# mux_sh_lite.net
KiCad netlist of a schematic drawn in EAGLE
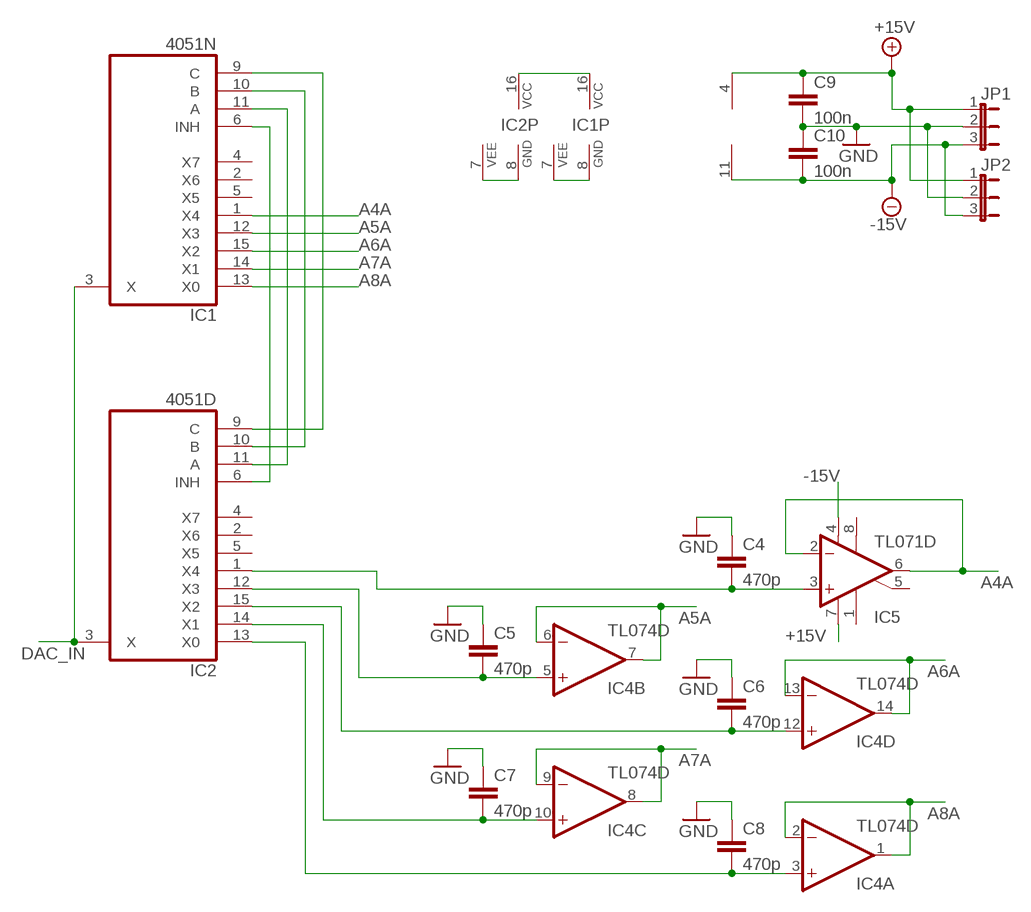
[diagram p0: schematic, sheet 1]

(export (version "E")
  (design (tool "Eeschema 10.0.6"))
  (components
    (comp (ref "C4")
      (value "470p")
      (footprint "eagle-import:0805")
      (libsource (lib "eagle-import") (part "CAP0805"))
    )
    (comp (ref "C5")
      (value "470p")
      (footprint "eagle-import:0805")
      (libsource (lib "eagle-import") (part "CAP0805"))
    )
    (comp (ref "C6")
      (value "470p")
      (footprint "eagle-import:0805")
      (libsource (lib "eagle-import") (part "CAP0805"))
    )
    (comp (ref "C7")
      (value "470p")
      (footprint "eagle-import:0805")
      (libsource (lib "eagle-import") (part "CAP0805"))
    )
    (comp (ref "C8")
      (value "470p")
      (footprint "eagle-import:0805")
      (libsource (lib "eagle-import") (part "CAP0805"))
    )
    (comp (ref "C9")
      (value "100n")
      (footprint "eagle-import:0805")
      (libsource (lib "eagle-import") (part "CAP0805"))
    )
    (comp (ref "C10")
      (value "100n")
      (footprint "eagle-import:0805")
      (libsource (lib "eagle-import") (part "CAP0805"))
    )
    (comp (ref "IC1")
      (value "4051N")
      (footprint "eagle-import:DIL16")
      (libsource (lib "eagle-import") (part "4051N"))
    )
    (comp (ref "IC2")
      (value "4051D")
      (footprint "eagle-import:SO16")
      (libsource (lib "eagle-import") (part "4051D"))
    )
    (comp (ref "IC4")
      (value "TL074D")
      (footprint "eagle-import:SO14")
      (libsource (lib "eagle-import") (part "TL074D"))
    )
    (comp (ref "IC5")
      (value "TL071D")
      (footprint "eagle-import:SO08")
      (libsource (lib "eagle-import") (part "TL071D"))
    )
    (comp (ref "JP1")
      (value "JP2E")
      (footprint "eagle-import:JP2")
      (libsource (lib "eagle-import") (part "JP2E"))
    )
    (comp (ref "JP2")
      (value "JP2E")
      (footprint "eagle-import:JP2")
      (libsource (lib "eagle-import") (part "JP2E"))
    )
  )
  (nets
    (net (code "1") (name "+15V") (class "Default")
      (node (ref "C9") (pin "1") (pinfunction "1_1") (pintype "passive"))
      (node (ref "IC4") (pin "4") (pinfunction "V+_4") (pintype "power_in"))
      (node (ref "IC5") (pin "7") (pinfunction "V+_7") (pintype "power_in"))
      (node (ref "JP1") (pin "1") (pinfunction "1_1") (pintype "passive"))
      (node (ref "JP2") (pin "1") (pinfunction "1_1") (pintype "passive"))
    )
    (net (code "2") (name "-15V") (class "Default")
      (node (ref "C10") (pin "2") (pinfunction "2_2") (pintype "passive"))
      (node (ref "IC4") (pin "11") (pinfunction "V-_11") (pintype "power_in"))
      (node (ref "IC5") (pin "4") (pinfunction "V-_4") (pintype "power_in"))
      (node (ref "JP1") (pin "3") (pinfunction "3_3") (pintype "passive"))
      (node (ref "JP2") (pin "3") (pinfunction "3_3") (pintype "passive"))
    )
    (net (code "3") (name "/A4A") (class "Default")
      (node (ref "IC1") (pin "1") (pinfunction "X4_1") (pintype "bidirectional"))
      (node (ref "IC5") (pin "2") (pinfunction "-IN_2") (pintype "input"))
      (node (ref "IC5") (pin "6") (pinfunction "OUT_6") (pintype "output"))
    )
    (net (code "4") (name "/A5A") (class "Default")
      (node (ref "IC1") (pin "12") (pinfunction "X3_12") (pintype "bidirectional"))
      (node (ref "IC4") (pin "6") (pinfunction "-IN_6") (pintype "input"))
      (node (ref "IC4") (pin "7") (pinfunction "OUT_7") (pintype "output"))
    )
    (net (code "5") (name "/A6A") (class "Default")
      (node (ref "IC1") (pin "15") (pinfunction "X2_15") (pintype "bidirectional"))
      (node (ref "IC4") (pin "13") (pinfunction "-IN_13") (pintype "input"))
      (node (ref "IC4") (pin "14") (pinfunction "OUT_14") (pintype "output"))
    )
    (net (code "6") (name "/A7A") (class "Default")
      (node (ref "IC1") (pin "14") (pinfunction "X1_14") (pintype "bidirectional"))
      (node (ref "IC4") (pin "8") (pinfunction "OUT_8") (pintype "output"))
      (node (ref "IC4") (pin "9") (pinfunction "-IN_9") (pintype "input"))
    )
    (net (code "7") (name "/A8A") (class "Default")
      (node (ref "IC1") (pin "13") (pinfunction "X0_13") (pintype "bidirectional"))
      (node (ref "IC4") (pin "1") (pinfunction "OUT_1") (pintype "output"))
      (node (ref "IC4") (pin "2") (pinfunction "-IN_2") (pintype "input"))
    )
    (net (code "8") (name "/DAC_IN") (class "Default")
      (node (ref "IC1") (pin "3") (pinfunction "X_3") (pintype "bidirectional"))
      (node (ref "IC2") (pin "3") (pinfunction "X_3") (pintype "bidirectional"))
    )
    (net (code "9") (name "GND") (class "Default")
      (node (ref "C10") (pin "1") (pinfunction "1_1") (pintype "passive"))
      (node (ref "C4") (pin "1") (pinfunction "1_1") (pintype "passive"))
      (node (ref "C5") (pin "1") (pinfunction "1_1") (pintype "passive"))
      (node (ref "C6") (pin "1") (pinfunction "1_1") (pintype "passive"))
      (node (ref "C7") (pin "1") (pinfunction "1_1") (pintype "passive"))
      (node (ref "C8") (pin "1") (pinfunction "1_1") (pintype "passive"))
      (node (ref "C9") (pin "2") (pinfunction "2_2") (pintype "passive"))
      (node (ref "JP1") (pin "2") (pinfunction "2_2") (pintype "passive"))
      (node (ref "JP2") (pin "2") (pinfunction "2_2") (pintype "passive"))
    )
    (net (code "10") (name "Net-(IC1A-A)") (class "Default")
      (node (ref "IC1") (pin "11") (pinfunction "A_11") (pintype "input"))
      (node (ref "IC2") (pin "11") (pinfunction "A_11") (pintype "input"))
    )
    (net (code "11") (name "Net-(IC1A-B)") (class "Default")
      (node (ref "IC1") (pin "10") (pinfunction "B_10") (pintype "input"))
      (node (ref "IC2") (pin "10") (pinfunction "B_10") (pintype "input"))
    )
    (net (code "12") (name "Net-(IC1A-C)") (class "Default")
      (node (ref "IC1") (pin "9") (pinfunction "C_9") (pintype "input"))
      (node (ref "IC2") (pin "9") (pinfunction "C_9") (pintype "input"))
    )
    (net (code "13") (name "Net-(IC1A-INH)") (class "Default")
      (node (ref "IC1") (pin "6") (pinfunction "INH_6") (pintype "input"))
      (node (ref "IC2") (pin "6") (pinfunction "INH_6") (pintype "input"))
    )
    (net (code "14") (name "Net-(IC1B-GND)") (class "Default")
      (node (ref "IC1") (pin "7") (pinfunction "VEE_7") (pintype "power_in"))
      (node (ref "IC1") (pin "8") (pinfunction "GND_8") (pintype "power_in"))
    )
    (net (code "15") (name "Net-(IC1B-VCC)") (class "Default")
      (node (ref "IC1") (pin "16") (pinfunction "VCC_16") (pintype "power_in"))
      (node (ref "IC2") (pin "16") (pinfunction "VCC_16") (pintype "power_in"))
    )
    (net (code "16") (name "Net-(IC2A-X0)") (class "Default")
      (node (ref "C8") (pin "2") (pinfunction "2_2") (pintype "passive"))
      (node (ref "IC2") (pin "13") (pinfunction "X0_13") (pintype "bidirectional"))
      (node (ref "IC4") (pin "3") (pinfunction "+IN_3") (pintype "input"))
    )
    (net (code "17") (name "Net-(IC2A-X1)") (class "Default")
      (node (ref "C7") (pin "2") (pinfunction "2_2") (pintype "passive"))
      (node (ref "IC2") (pin "14") (pinfunction "X1_14") (pintype "bidirectional"))
      (node (ref "IC4") (pin "10") (pinfunction "+IN_10") (pintype "input"))
    )
    (net (code "18") (name "Net-(IC2A-X2)") (class "Default")
      (node (ref "C6") (pin "2") (pinfunction "2_2") (pintype "passive"))
      (node (ref "IC2") (pin "15") (pinfunction "X2_15") (pintype "bidirectional"))
      (node (ref "IC4") (pin "12") (pinfunction "+IN_12") (pintype "input"))
    )
    (net (code "19") (name "Net-(IC2A-X3)") (class "Default")
      (node (ref "C5") (pin "2") (pinfunction "2_2") (pintype "passive"))
      (node (ref "IC2") (pin "12") (pinfunction "X3_12") (pintype "bidirectional"))
      (node (ref "IC4") (pin "5") (pinfunction "+IN_5") (pintype "input"))
    )
    (net (code "20") (name "Net-(IC2A-X4)") (class "Default")
      (node (ref "C4") (pin "2") (pinfunction "2_2") (pintype "passive"))
      (node (ref "IC2") (pin "1") (pinfunction "X4_1") (pintype "bidirectional"))
      (node (ref "IC5") (pin "3") (pinfunction "+IN_3") (pintype "input"))
    )
    (net (code "21") (name "Net-(IC2B-GND)") (class "Default")
      (node (ref "IC2") (pin "7") (pinfunction "VEE_7") (pintype "power_in"))
      (node (ref "IC2") (pin "8") (pinfunction "GND_8") (pintype "power_in"))
    )
    (net (code "22") (name "unconnected-(IC1A-X5-Pad5)") (class "Default")
      (node (ref "IC1") (pin "5") (pinfunction "X5_5") (pintype "bidirectional"))
    )
    (net (code "23") (name "unconnected-(IC1A-X6-Pad2)") (class "Default")
      (node (ref "IC1") (pin "2") (pinfunction "X6_2") (pintype "bidirectional"))
    )
    (net (code "24") (name "unconnected-(IC1A-X7-Pad4)") (class "Default")
      (node (ref "IC1") (pin "4") (pinfunction "X7_4") (pintype "bidirectional"))
    )
    (net (code "25") (name "unconnected-(IC2A-X5-Pad5)") (class "Default")
      (node (ref "IC2") (pin "5") (pinfunction "X5_5") (pintype "bidirectional"))
    )
    (net (code "26") (name "unconnected-(IC2A-X6-Pad2)") (class "Default")
      (node (ref "IC2") (pin "2") (pinfunction "X6_2") (pintype "bidirectional"))
    )
    (net (code "27") (name "unconnected-(IC2A-X7-Pad4)") (class "Default")
      (node (ref "IC2") (pin "4") (pinfunction "X7_4") (pintype "bidirectional"))
    )
    (net (code "28") (name "unconnected-(IC5-ON1-Pad1)") (class "Default")
      (node (ref "IC5") (pin "1") (pinfunction "ON1_1") (pintype "passive"))
    )
    (net (code "29") (name "unconnected-(IC5-ON2-Pad5)") (class "Default")
      (node (ref "IC5") (pin "5") (pinfunction "ON2_5") (pintype "passive"))
    )
    (net (code "30") (name "unconnected-(IC5-OPT-Pad8)") (class "Default")
      (node (ref "IC5") (pin "8") (pinfunction "OPT_8") (pintype "passive"))
    )
  )
)
